# PERSONCOUNTERWITHLED.net
KiCad netlist of a schematic drawn in EasyEDA
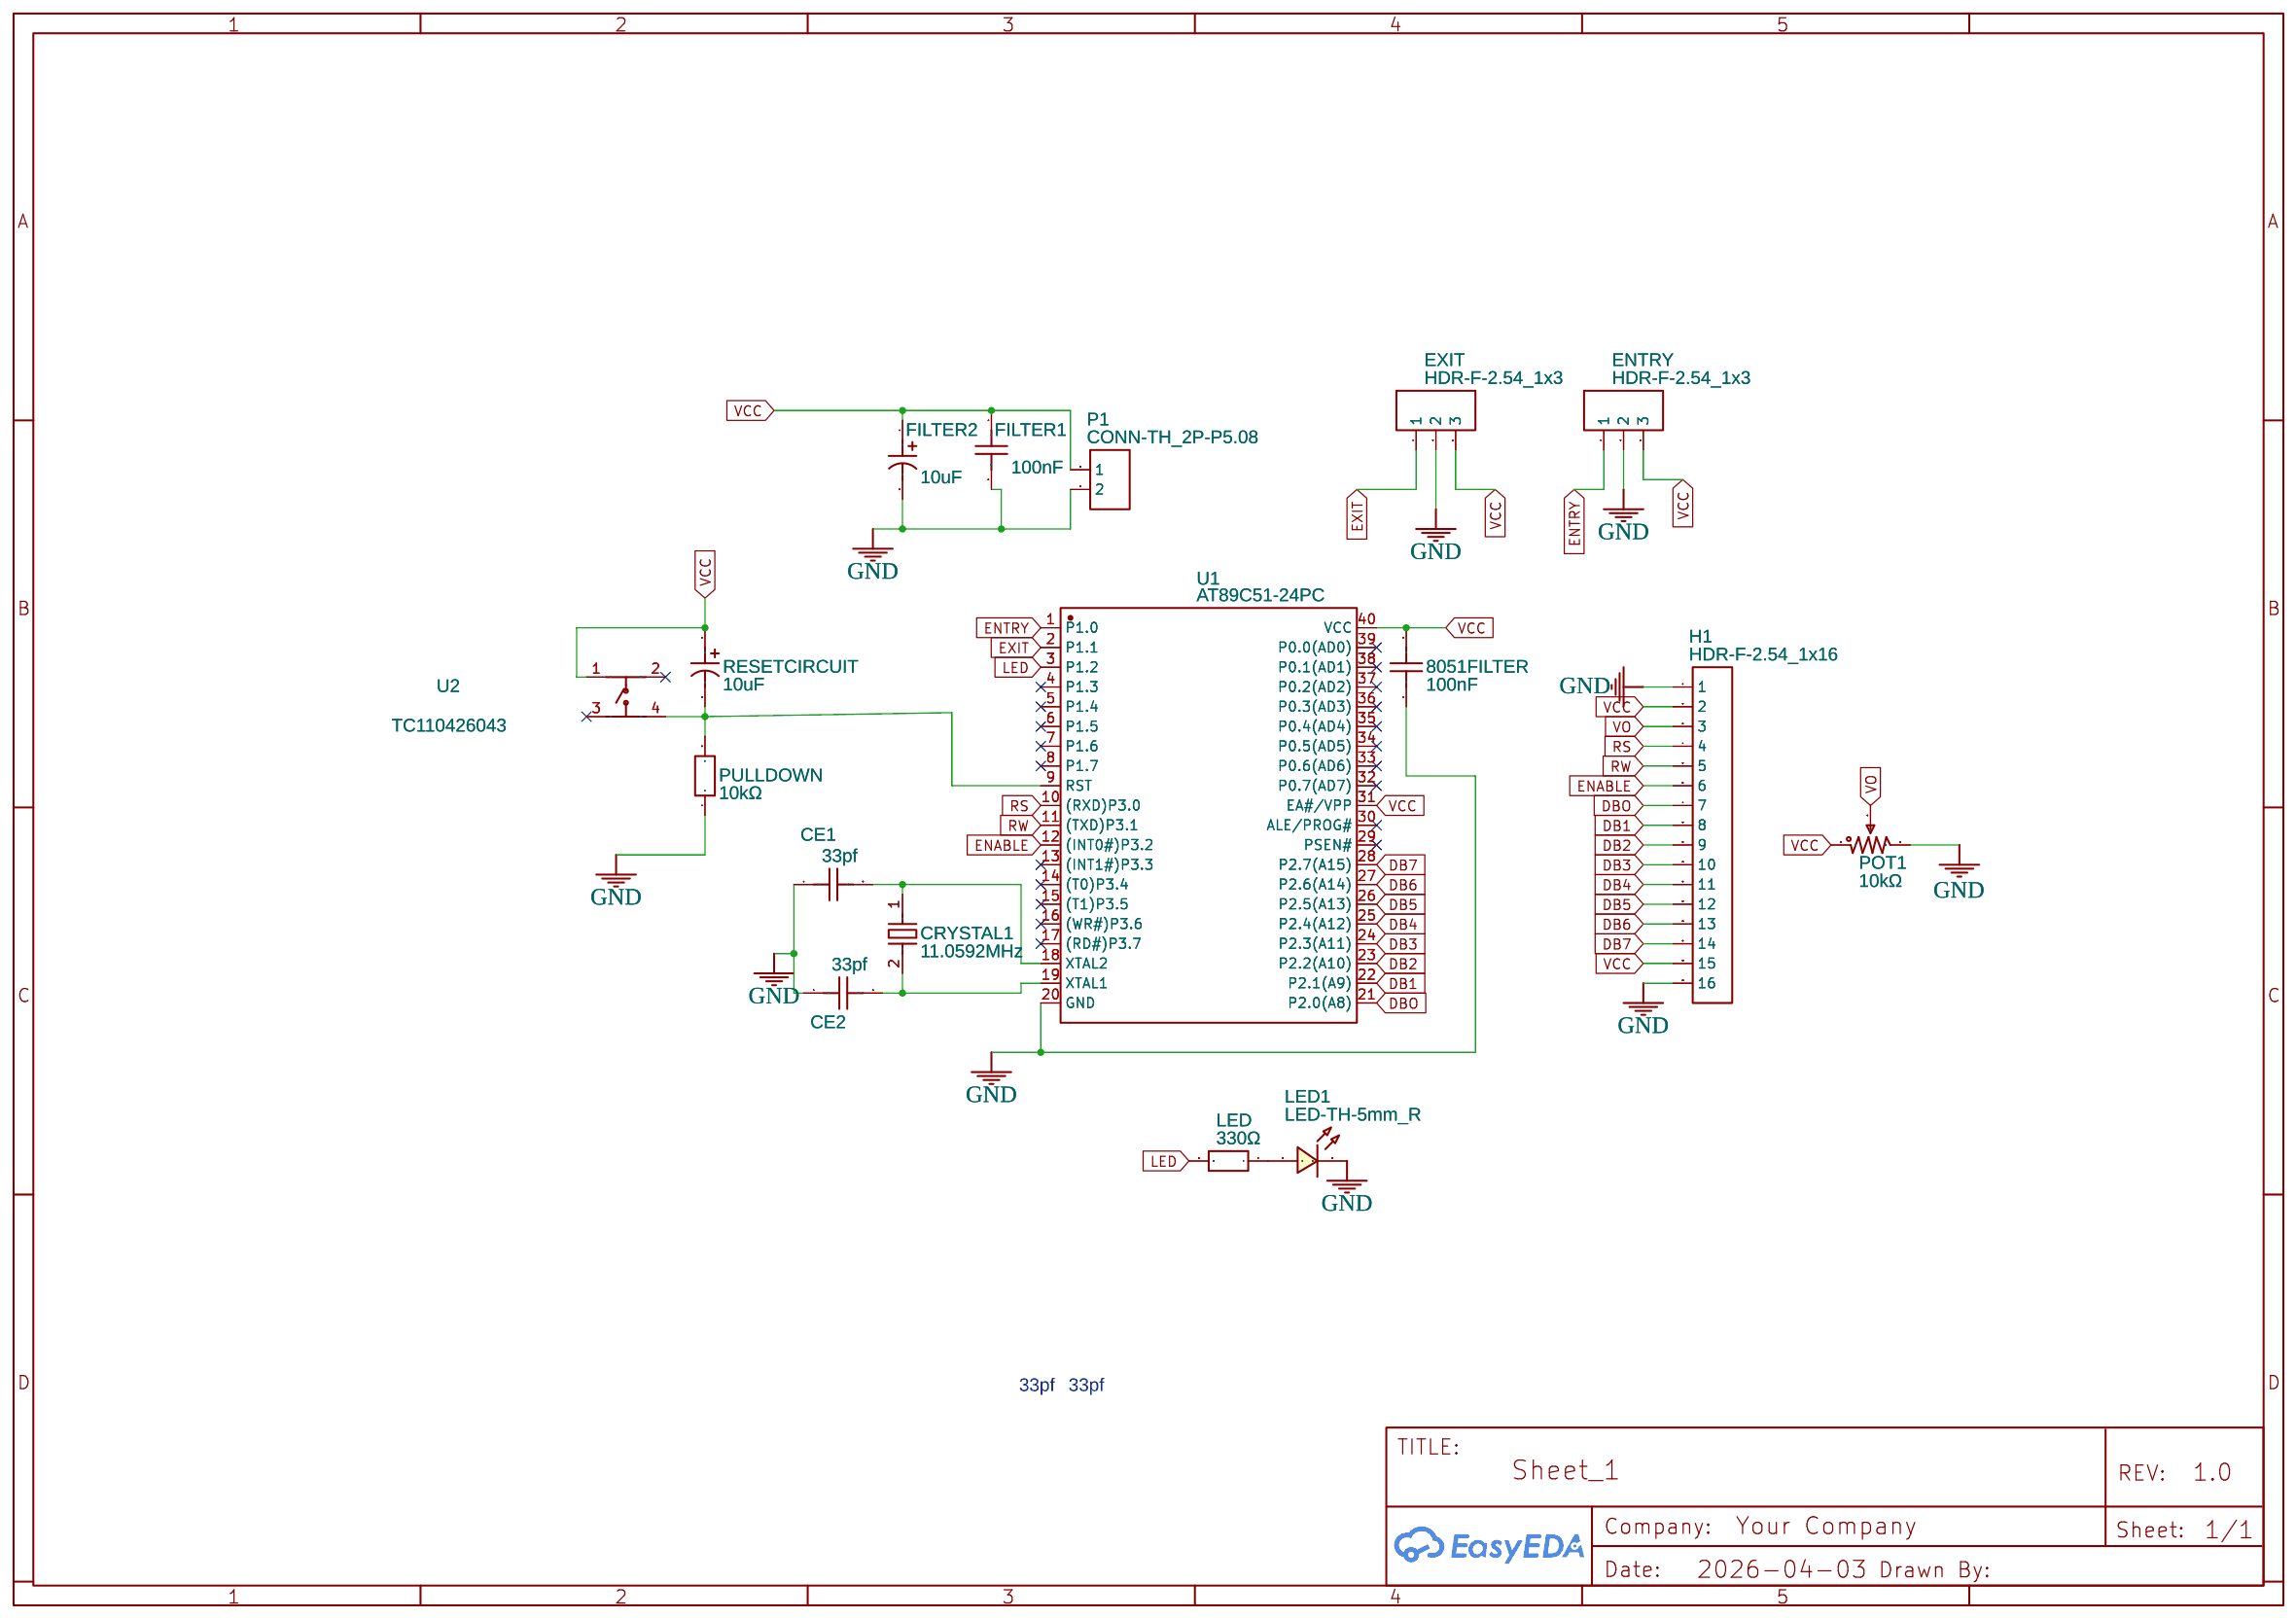
[diagram p0: schematic sheet]

(export (version "E")
  (design (tool "Eeschema 10.0.6"))
  (components
    (comp (ref "8051FILTER")
      (value "100nF")
      (fields
        (field (name "Manufacturer Part") "CC1H104ZC1PD3F5P3003")
        (field (name "Manufacturer") "Dersonic(德尔创)")
      )
      (libsource (lib "") (part "CC1H104ZC1PD3F5P3003_2"))
    )
    (comp (ref "CE1")
      (value "33pf")
      (fields
        (field (name "Manufacturer Part") "CC1H104ZC1PD3F5P3003")
        (field (name "Manufacturer") "Dersonic(德尔创)")
      )
      (libsource (lib "") (part "CC1H104ZC1PD3F5P3003"))
    )
    (comp (ref "CE2")
      (value "33pf")
      (fields
        (field (name "Manufacturer Part") "CC1H104ZC1PD3F5P3003")
        (field (name "Manufacturer") "Dersonic(德尔创)")
      )
      (libsource (lib "") (part "CC1H104ZC1PD3F5P3003"))
    )
    (comp (ref "CRYSTAL1")
      (value "11.0592MHz")
      (fields (field (name "Manufacturer Part") "SP2011M05920001") (field (name "Manufacturer") "HUAXIN(华昕)"))
      (libsource (lib "") (part "SP2011M05920001"))
    )
    (comp (ref "ENTRY") (value "HDR-F-2.54_1x3") (libsource (lib "") (part "HDR-F-2.54_1x3_1")))
    (comp (ref "EXIT") (value "HDR-F-2.54_1x3") (libsource (lib "") (part "HDR-F-2.54_1x3")))
    (comp (ref "FILTER1")
      (value "100nF")
      (fields
        (field (name "Manufacturer Part") "CC1H104ZC1PD3F5P3003")
        (field (name "Manufacturer") "Dersonic(德尔创)")
      )
      (libsource (lib "") (part "CC1H104ZC1PD3F5P3003_1"))
    )
    (comp (ref "FILTER2")
      (value "10uF")
      (fields (field (name "Manufacturer Part") "10UF50VC110GL") (field (name "Manufacturer") "Econd(米朗电子)"))
      (libsource (lib "") (part "10UF50VC110GL"))
    )
    (comp (ref "H1") (value "HDR-F-2.54_1x16") (libsource (lib "") (part "HDR-F-2.54_1x16")))
    (comp (ref "LED")
      (value "330Ω")
      (fields
        (field (name "Manufacturer Part") "MF006FF2202A50")
        (field (name "Manufacturer") "UNI-ROYAL(厚声)")
      )
      (libsource (lib "") (part "MF006FF2202A50_1"))
    )
    (comp (ref "LED1")
      (value "LED-TH-5mm_R")
      (fields
        (field (name "Manufacturer Part") "333-2SURD/S530-A3")
        (field (name "Manufacturer") "EVERLIGHT(台湾亿光)")
      )
      (libsource (lib "") (part "LED-TH-5mm_R"))
    )
    (comp (ref "P1") (value "CONN-TH_2P-P5.08") (libsource (lib "") (part "CONN-TH_2P-P5.08")))
    (comp (ref "POT1")
      (value "10kΩ")
      (fields (field (name "Manufacturer Part") "RM065-103(10K)") (field (name "Manufacturer") "BOCHEN(博晨)"))
      (libsource (lib "") (part "RM065-103(10K)"))
    )
    (comp (ref "PULLDOWN")
      (value "10kΩ")
      (fields
        (field (name "Manufacturer Part") "MF006FF2202A50")
        (field (name "Manufacturer") "UNI-ROYAL(厚声)")
      )
      (libsource (lib "") (part "MF006FF2202A50"))
    )
    (comp (ref "RESETCIRCUIT")
      (value "10uF")
      (fields (field (name "Manufacturer Part") "10UF50VC110GL") (field (name "Manufacturer") "Econd(米朗电子)"))
      (libsource (lib "") (part "10UF50VC110GL_1"))
    )
    (comp (ref "U1")
      (value "AT89C51-24PC")
      (fields (field (name "Manufacturer") "MICROCHIP(美国微芯)"))
      (libsource (lib "") (part "AT89C51-24PC"))
    )
    (comp (ref "U2")
      (value "TC110426043")
      (fields (field (name "Manufacturer") "HanElectricity(瀚源)"))
      (libsource (lib "") (part "TC110426043"))
    )
  )
  (nets
    (net (code "1") (name "DB1") (class "Default")
      (node (ref "H1") (pin "8") (pinfunction "8_8") (pintype "unspecified"))
      (node (ref "U1") (pin "22") (pinfunction "P2.1(A9)_22") (pintype "unspecified"))
    )
    (net (code "2") (name "DB2") (class "Default")
      (node (ref "H1") (pin "9") (pinfunction "9_9") (pintype "unspecified"))
      (node (ref "U1") (pin "23") (pinfunction "P2.2(A10)_23") (pintype "unspecified"))
    )
    (net (code "3") (name "DB3") (class "Default")
      (node (ref "H1") (pin "10") (pinfunction "10_10") (pintype "unspecified"))
      (node (ref "U1") (pin "24") (pinfunction "P2.3(A11)_24") (pintype "unspecified"))
    )
    (net (code "4") (name "DB4") (class "Default")
      (node (ref "H1") (pin "11") (pinfunction "11_11") (pintype "unspecified"))
      (node (ref "U1") (pin "25") (pinfunction "P2.4(A12)_25") (pintype "unspecified"))
    )
    (net (code "5") (name "DB5") (class "Default")
      (node (ref "H1") (pin "12") (pinfunction "12_12") (pintype "unspecified"))
      (node (ref "U1") (pin "26") (pinfunction "P2.5(A13)_26") (pintype "unspecified"))
    )
    (net (code "6") (name "DB6") (class "Default")
      (node (ref "H1") (pin "13") (pinfunction "13_13") (pintype "unspecified"))
      (node (ref "U1") (pin "27") (pinfunction "P2.6(A14)_27") (pintype "unspecified"))
    )
    (net (code "7") (name "DB7") (class "Default")
      (node (ref "H1") (pin "14") (pinfunction "14_14") (pintype "unspecified"))
      (node (ref "U1") (pin "28") (pinfunction "P2.7(A15)_28") (pintype "unspecified"))
    )
    (net (code "8") (name "DBO") (class "Default")
      (node (ref "H1") (pin "7") (pinfunction "7_7") (pintype "unspecified"))
      (node (ref "U1") (pin "21") (pinfunction "P2.0(A8)_21") (pintype "unspecified"))
    )
    (net (code "9") (name "ENABLE") (class "Default")
      (node (ref "H1") (pin "6") (pinfunction "6_6") (pintype "unspecified"))
      (node (ref "U1") (pin "12") (pinfunction "(INT0#)P3.2_12") (pintype "unspecified"))
    )
    (net (code "10") (name "ENTRY") (class "Default")
      (node (ref "ENTRY") (pin "1") (pinfunction "1_1") (pintype "input"))
      (node (ref "U1") (pin "1") (pinfunction "P1.0_1") (pintype "unspecified"))
    )
    (net (code "11") (name "EXIT") (class "Default")
      (node (ref "EXIT") (pin "1") (pinfunction "1_1") (pintype "input"))
      (node (ref "U1") (pin "2") (pinfunction "P1.1_2") (pintype "unspecified"))
    )
    (net (code "12") (name "GND") (class "Default")
      (node (ref "8051FILTER") (pin "2") (pinfunction "2_2") (pintype "unspecified"))
      (node (ref "CE1") (pin "1") (pinfunction "1_1") (pintype "unspecified"))
      (node (ref "CE2") (pin "1") (pinfunction "1_1") (pintype "unspecified"))
      (node (ref "ENTRY") (pin "2") (pinfunction "2_2") (pintype "input"))
      (node (ref "EXIT") (pin "2") (pinfunction "2_2") (pintype "input"))
      (node (ref "FILTER1") (pin "2") (pinfunction "2_2") (pintype "unspecified"))
      (node (ref "FILTER2") (pin "2") (pinfunction "2_2") (pintype "input"))
      (node (ref "H1") (pin "1") (pinfunction "1_1") (pintype "unspecified"))
      (node (ref "H1") (pin "16") (pinfunction "16_16") (pintype "unspecified"))
      (node (ref "LED1") (pin "2") (pinfunction "2_2") (pintype "unspecified"))
      (node (ref "P1") (pin "2") (pinfunction "2_2") (pintype "unspecified"))
      (node (ref "POT1") (pin "3") (pinfunction "3_3") (pintype "unspecified"))
      (node (ref "PULLDOWN") (pin "1") (pinfunction "1_1") (pintype "unspecified"))
      (node (ref "U1") (pin "20") (pinfunction "GND_20") (pintype "unspecified"))
    )
    (net (code "13") (name "LED") (class "Default")
      (node (ref "LED") (pin "2") (pinfunction "2_2") (pintype "unspecified"))
      (node (ref "U1") (pin "3") (pinfunction "P1.2_3") (pintype "unspecified"))
    )
    (net (code "14") (name "Net-(LED-Pad1)") (class "Default")
      (node (ref "LED") (pin "1") (pinfunction "1_1") (pintype "unspecified"))
      (node (ref "LED1") (pin "1") (pinfunction "1_1") (pintype "unspecified"))
    )
    (net (code "15") (name "Net-(U1-RST)") (class "Default")
      (node (ref "PULLDOWN") (pin "2") (pinfunction "2_2") (pintype "unspecified"))
      (node (ref "RESETCIRCUIT") (pin "2") (pinfunction "2_2") (pintype "input"))
      (node (ref "U1") (pin "9") (pinfunction "RST_9") (pintype "unspecified"))
      (node (ref "U2") (pin "4") (pinfunction "4_4") (pintype "unspecified"))
    )
    (net (code "16") (name "Net-(U1-XTAL1)") (class "Default")
      (node (ref "CE2") (pin "2") (pinfunction "2_2") (pintype "unspecified"))
      (node (ref "CRYSTAL1") (pin "2") (pinfunction "2_2") (pintype "unspecified"))
      (node (ref "U1") (pin "19") (pinfunction "XTAL1_19") (pintype "unspecified"))
    )
    (net (code "17") (name "Net-(U1-XTAL2)") (class "Default")
      (node (ref "CE1") (pin "2") (pinfunction "2_2") (pintype "unspecified"))
      (node (ref "CRYSTAL1") (pin "1") (pinfunction "1_1") (pintype "unspecified"))
      (node (ref "U1") (pin "18") (pinfunction "XTAL2_18") (pintype "unspecified"))
    )
    (net (code "18") (name "RS") (class "Default")
      (node (ref "H1") (pin "4") (pinfunction "4_4") (pintype "unspecified"))
      (node (ref "U1") (pin "10") (pinfunction "(RXD)P3.0_10") (pintype "unspecified"))
    )
    (net (code "19") (name "RW") (class "Default")
      (node (ref "H1") (pin "5") (pinfunction "5_5") (pintype "unspecified"))
      (node (ref "U1") (pin "11") (pinfunction "(TXD)P3.1_11") (pintype "unspecified"))
    )
    (net (code "20") (name "VCC") (class "Default")
      (node (ref "8051FILTER") (pin "1") (pinfunction "1_1") (pintype "unspecified"))
      (node (ref "ENTRY") (pin "3") (pinfunction "3_3") (pintype "input"))
      (node (ref "EXIT") (pin "3") (pinfunction "3_3") (pintype "input"))
      (node (ref "FILTER1") (pin "1") (pinfunction "1_1") (pintype "unspecified"))
      (node (ref "FILTER2") (pin "1") (pinfunction "1_1") (pintype "input"))
      (node (ref "H1") (pin "15") (pinfunction "15_15") (pintype "unspecified"))
      (node (ref "H1") (pin "2") (pinfunction "2_2") (pintype "unspecified"))
      (node (ref "P1") (pin "1") (pinfunction "1_1") (pintype "unspecified"))
      (node (ref "POT1") (pin "1") (pinfunction "1_1") (pintype "unspecified"))
      (node (ref "RESETCIRCUIT") (pin "1") (pinfunction "1_1") (pintype "input"))
      (node (ref "U1") (pin "31") (pinfunction "EA#/VPP_31") (pintype "unspecified"))
      (node (ref "U1") (pin "40") (pinfunction "VCC_40") (pintype "unspecified"))
      (node (ref "U2") (pin "1") (pinfunction "1_1") (pintype "unspecified"))
    )
    (net (code "21") (name "VO") (class "Default")
      (node (ref "H1") (pin "3") (pinfunction "3_3") (pintype "unspecified"))
      (node (ref "POT1") (pin "2") (pinfunction "2_2") (pintype "unspecified"))
    )
    (net (code "22") (name "unconnected-(U1-(INT1#)P3.3-Pad13)") (class "Default")
      (node (ref "U1") (pin "13") (pinfunction "(INT1#)P3.3_13") (pintype "unspecified+no_connect"))
    )
    (net (code "23") (name "unconnected-(U1-(RD#)P3.7-Pad17)") (class "Default")
      (node (ref "U1") (pin "17") (pinfunction "(RD#)P3.7_17") (pintype "unspecified+no_connect"))
    )
    (net (code "24") (name "unconnected-(U1-(T0)P3.4-Pad14)") (class "Default")
      (node (ref "U1") (pin "14") (pinfunction "(T0)P3.4_14") (pintype "unspecified+no_connect"))
    )
    (net (code "25") (name "unconnected-(U1-(T1)P3.5-Pad15)") (class "Default")
      (node (ref "U1") (pin "15") (pinfunction "(T1)P3.5_15") (pintype "unspecified+no_connect"))
    )
    (net (code "26") (name "unconnected-(U1-(WR#)P3.6-Pad16)") (class "Default")
      (node (ref "U1") (pin "16") (pinfunction "(WR#)P3.6_16") (pintype "unspecified+no_connect"))
    )
    (net (code "27") (name "unconnected-(U1-ALE{slash}PROG#-Pad30)") (class "Default")
      (node (ref "U1") (pin "30") (pinfunction "ALE/PROG#_30") (pintype "unspecified+no_connect"))
    )
    (net (code "28") (name "unconnected-(U1-P0.0(AD0)-Pad39)") (class "Default")
      (node (ref "U1") (pin "39") (pinfunction "P0.0(AD0)_39") (pintype "unspecified+no_connect"))
    )
    (net (code "29") (name "unconnected-(U1-P0.1(AD1)-Pad38)") (class "Default")
      (node (ref "U1") (pin "38") (pinfunction "P0.1(AD1)_38") (pintype "unspecified+no_connect"))
    )
    (net (code "30") (name "unconnected-(U1-P0.2(AD2)-Pad37)") (class "Default")
      (node (ref "U1") (pin "37") (pinfunction "P0.2(AD2)_37") (pintype "unspecified+no_connect"))
    )
    (net (code "31") (name "unconnected-(U1-P0.3(AD3)-Pad36)") (class "Default")
      (node (ref "U1") (pin "36") (pinfunction "P0.3(AD3)_36") (pintype "unspecified+no_connect"))
    )
    (net (code "32") (name "unconnected-(U1-P0.4(AD4)-Pad35)") (class "Default")
      (node (ref "U1") (pin "35") (pinfunction "P0.4(AD4)_35") (pintype "unspecified+no_connect"))
    )
    (net (code "33") (name "unconnected-(U1-P0.5(AD5)-Pad34)") (class "Default")
      (node (ref "U1") (pin "34") (pinfunction "P0.5(AD5)_34") (pintype "unspecified+no_connect"))
    )
    (net (code "34") (name "unconnected-(U1-P0.6(AD6)-Pad33)") (class "Default")
      (node (ref "U1") (pin "33") (pinfunction "P0.6(AD6)_33") (pintype "unspecified+no_connect"))
    )
    (net (code "35") (name "unconnected-(U1-P0.7(AD7)-Pad32)") (class "Default")
      (node (ref "U1") (pin "32") (pinfunction "P0.7(AD7)_32") (pintype "unspecified+no_connect"))
    )
    (net (code "36") (name "unconnected-(U1-P1.3-Pad4)") (class "Default")
      (node (ref "U1") (pin "4") (pinfunction "P1.3_4") (pintype "unspecified+no_connect"))
    )
    (net (code "37") (name "unconnected-(U1-P1.4-Pad5)") (class "Default")
      (node (ref "U1") (pin "5") (pinfunction "P1.4_5") (pintype "unspecified+no_connect"))
    )
    (net (code "38") (name "unconnected-(U1-P1.5-Pad6)") (class "Default")
      (node (ref "U1") (pin "6") (pinfunction "P1.5_6") (pintype "unspecified+no_connect"))
    )
    (net (code "39") (name "unconnected-(U1-P1.6-Pad7)") (class "Default")
      (node (ref "U1") (pin "7") (pinfunction "P1.6_7") (pintype "unspecified+no_connect"))
    )
    (net (code "40") (name "unconnected-(U1-P1.7-Pad8)") (class "Default")
      (node (ref "U1") (pin "8") (pinfunction "P1.7_8") (pintype "unspecified+no_connect"))
    )
    (net (code "41") (name "unconnected-(U1-PSEN#-Pad29)") (class "Default")
      (node (ref "U1") (pin "29") (pinfunction "PSEN#_29") (pintype "unspecified+no_connect"))
    )
    (net (code "42") (name "unconnected-(U2-Pad2)") (class "Default")
      (node (ref "U2") (pin "2") (pinfunction "2_2") (pintype "unspecified+no_connect"))
    )
    (net (code "43") (name "unconnected-(U2-Pad3)") (class "Default")
      (node (ref "U2") (pin "3") (pinfunction "3_3") (pintype "unspecified+no_connect"))
    )
  )
)
